# Placa_V_5.net
KiCad netlist of a schematic drawn in EAGLE
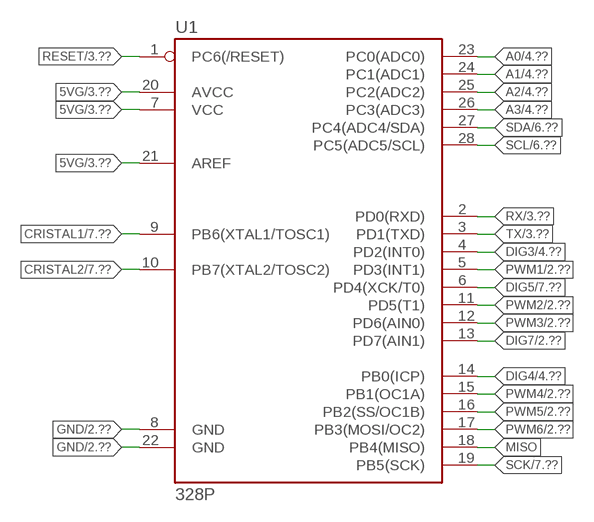
[diagram p0: schematic, sheet 1]
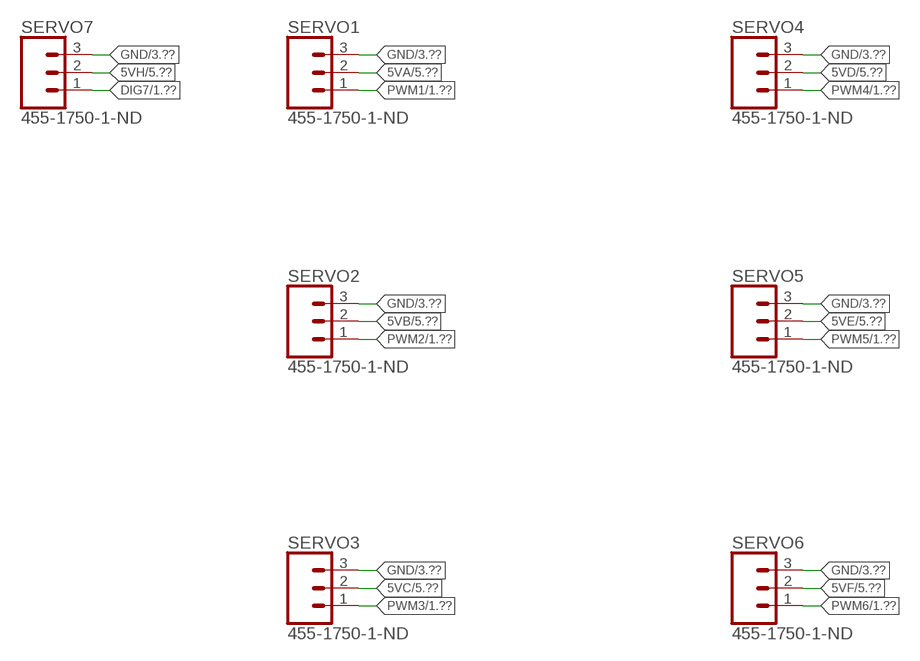
[diagram p1: schematic, sheet 2]
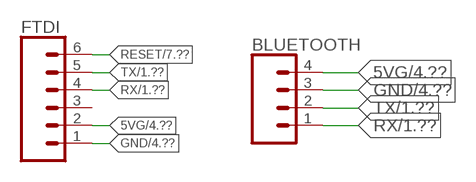
[diagram p2: schematic, sheet 3]
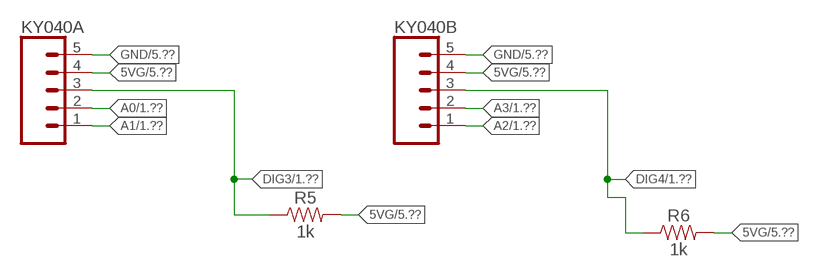
[diagram p3: schematic, sheet 4]
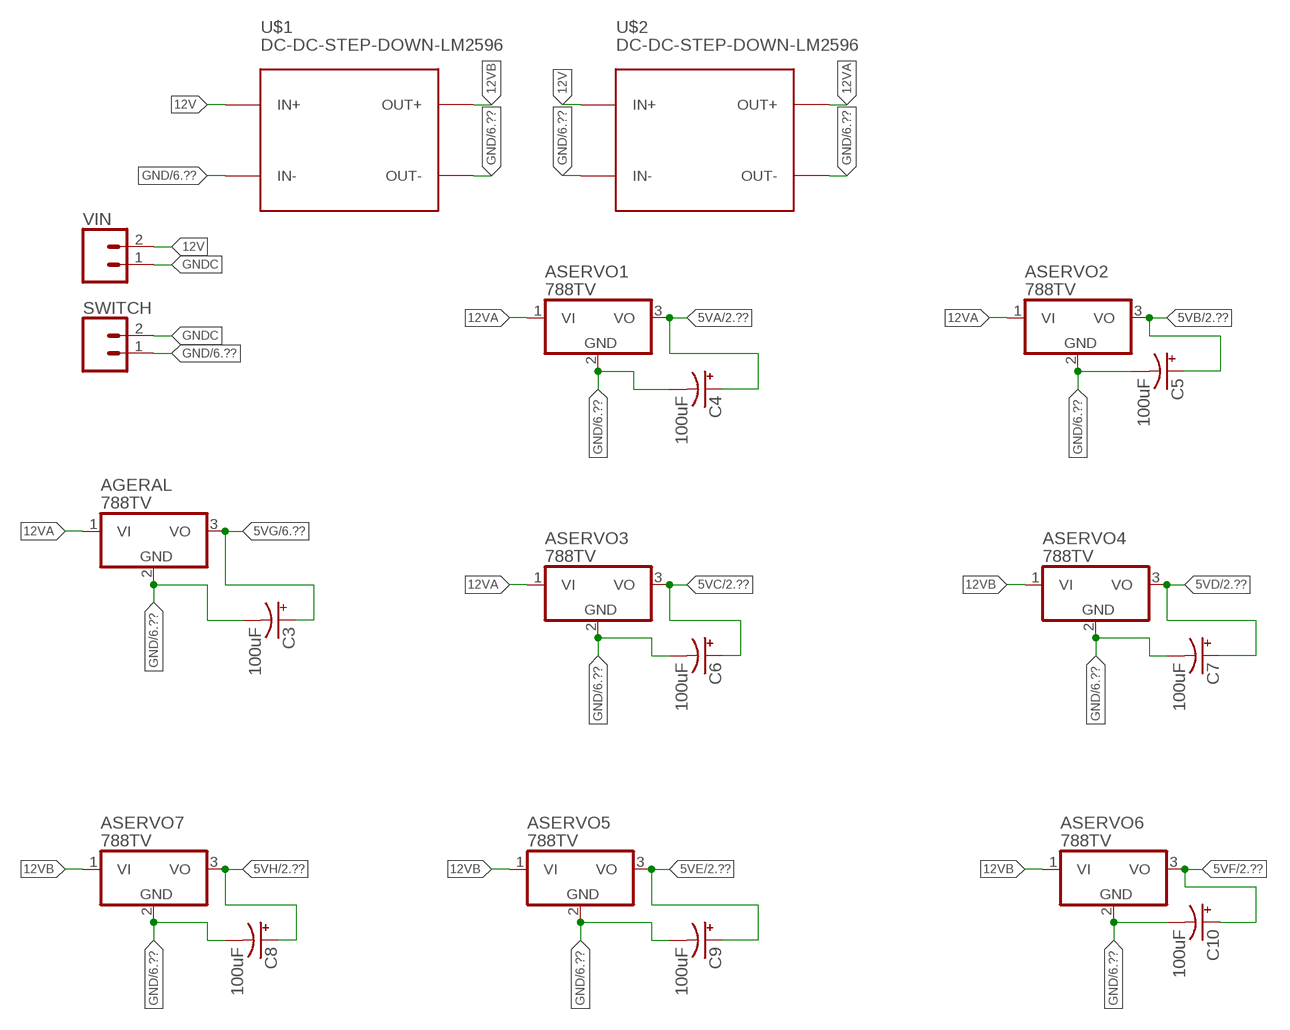
[diagram p4: schematic, sheet 5]
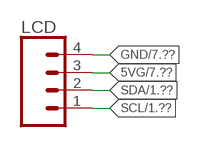
[diagram p5: schematic, sheet 6]
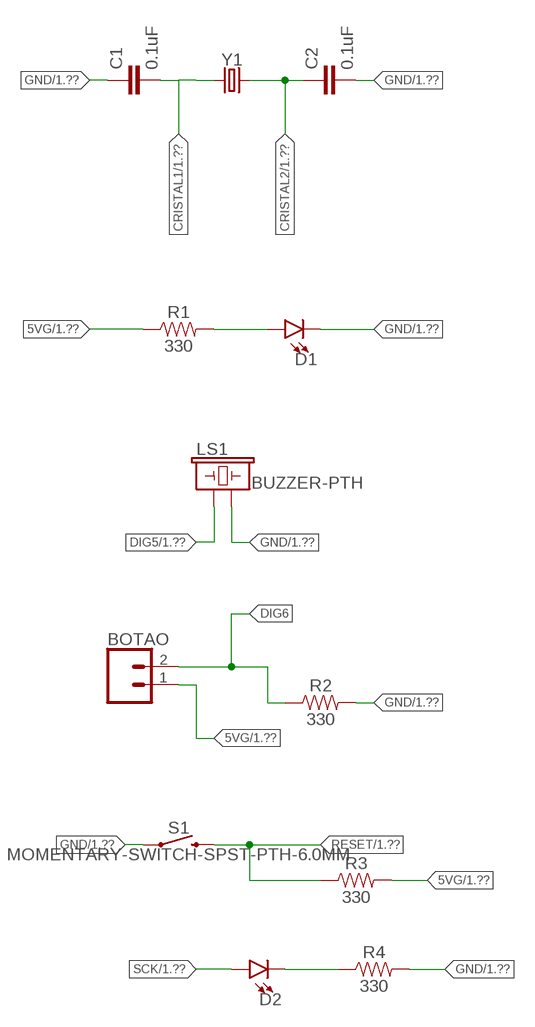
[diagram p6: schematic, sheet 7]

(export (version "E")
  (design (tool "Eeschema 10.0.6"))
  (components
    (comp (ref "AGERAL")
      (value "788TV")
      (footprint "eagle-import:TO220V")
      (libsource (lib "eagle-import") (part "78TV8"))
    )
    (comp (ref "ASERVO1")
      (value "788TV")
      (footprint "eagle-import:TO220V")
      (libsource (lib "eagle-import") (part "78TV8"))
    )
    (comp (ref "ASERVO2")
      (value "788TV")
      (footprint "eagle-import:TO220V")
      (libsource (lib "eagle-import") (part "78TV8"))
    )
    (comp (ref "ASERVO3")
      (value "788TV")
      (footprint "eagle-import:TO220V")
      (libsource (lib "eagle-import") (part "78TV8"))
    )
    (comp (ref "ASERVO4")
      (value "788TV")
      (footprint "eagle-import:TO220V")
      (libsource (lib "eagle-import") (part "78TV8"))
    )
    (comp (ref "ASERVO5")
      (value "788TV")
      (footprint "eagle-import:TO220V")
      (libsource (lib "eagle-import") (part "78TV8"))
    )
    (comp (ref "ASERVO6")
      (value "788TV")
      (footprint "eagle-import:TO220V")
      (libsource (lib "eagle-import") (part "78TV8"))
    )
    (comp (ref "ASERVO7")
      (value "788TV")
      (footprint "eagle-import:TO220V")
      (libsource (lib "eagle-import") (part "78TV8"))
    )
    (comp (ref "C3")
      (value "100uF")
      (footprint "eagle-import:CPOL-RADIAL-2.5MM-6.5MM")
      (libsource (lib "eagle-import") (part "100UF-POLAR-RADIAL-2.5MM-25V-20%"))
    )
    (comp (ref "C4")
      (value "100uF")
      (footprint "eagle-import:CPOL-RADIAL-2.5MM-6.5MM")
      (libsource (lib "eagle-import") (part "100UF-POLAR-RADIAL-2.5MM-25V-20%"))
    )
    (comp (ref "C5")
      (value "100uF")
      (footprint "eagle-import:CPOL-RADIAL-2.5MM-6.5MM")
      (libsource (lib "eagle-import") (part "100UF-POLAR-RADIAL-2.5MM-25V-20%"))
    )
    (comp (ref "C6")
      (value "100uF")
      (footprint "eagle-import:CPOL-RADIAL-2.5MM-6.5MM")
      (libsource (lib "eagle-import") (part "100UF-POLAR-RADIAL-2.5MM-25V-20%"))
    )
    (comp (ref "C7")
      (value "100uF")
      (footprint "eagle-import:CPOL-RADIAL-2.5MM-6.5MM")
      (libsource (lib "eagle-import") (part "100UF-POLAR-RADIAL-2.5MM-25V-20%"))
    )
    (comp (ref "C8")
      (value "100uF")
      (footprint "eagle-import:CPOL-RADIAL-2.5MM-6.5MM")
      (libsource (lib "eagle-import") (part "100UF-POLAR-RADIAL-2.5MM-25V-20%"))
    )
    (comp (ref "C9")
      (value "100uF")
      (footprint "eagle-import:CPOL-RADIAL-2.5MM-6.5MM")
      (libsource (lib "eagle-import") (part "100UF-POLAR-RADIAL-2.5MM-25V-20%"))
    )
    (comp (ref "C10")
      (value "100uF")
      (footprint "eagle-import:CPOL-RADIAL-2.5MM-6.5MM")
      (libsource (lib "eagle-import") (part "100UF-POLAR-RADIAL-2.5MM-25V-20%"))
    )
    (comp (ref "SWITCH")
      (value "CONN_02")
      (footprint "eagle-import:1X02")
      (libsource (lib "eagle-import") (part "CONN_02"))
    )
    (comp (ref "U$1")
      (value "DC-DC-STEP-DOWN-LM2596")
      (footprint "eagle-import:DC-DC-STEP-DOWN-LM2596")
      (libsource (lib "eagle-import") (part "DC-DC-STEP-DOWN-LM2596"))
    )
    (comp (ref "U$2")
      (value "DC-DC-STEP-DOWN-LM2596")
      (footprint "eagle-import:DC-DC-STEP-DOWN-LM2596")
      (libsource (lib "eagle-import") (part "DC-DC-STEP-DOWN-LM2596"))
    )
    (comp (ref "VIN")
      (value "CONN_02")
      (footprint "eagle-import:1X02")
      (libsource (lib "eagle-import") (part "CONN_02"))
    )
    (comp (ref "SERVO1")
      (value "455-1750-1-ND")
      (footprint "eagle-import:1X03")
      (libsource (lib "eagle-import") (part "CONN_03"))
    )
    (comp (ref "SERVO2")
      (value "455-1750-1-ND")
      (footprint "eagle-import:1X03")
      (libsource (lib "eagle-import") (part "CONN_03"))
    )
    (comp (ref "SERVO3")
      (value "455-1750-1-ND")
      (footprint "eagle-import:1X03")
      (libsource (lib "eagle-import") (part "CONN_03"))
    )
    (comp (ref "SERVO4")
      (value "455-1750-1-ND")
      (footprint "eagle-import:1X03")
      (libsource (lib "eagle-import") (part "CONN_03"))
    )
    (comp (ref "SERVO5")
      (value "455-1750-1-ND")
      (footprint "eagle-import:1X03")
      (libsource (lib "eagle-import") (part "CONN_03"))
    )
    (comp (ref "SERVO6")
      (value "455-1750-1-ND")
      (footprint "eagle-import:1X03")
      (libsource (lib "eagle-import") (part "CONN_03"))
    )
    (comp (ref "SERVO7")
      (value "455-1750-1-ND")
      (footprint "eagle-import:1X03")
      (libsource (lib "eagle-import") (part "CONN_03"))
    )
    (comp (ref "KY040A")
      (value "CONN_05")
      (footprint "eagle-import:1X05")
      (libsource (lib "eagle-import") (part "CONN_05"))
    )
    (comp (ref "KY040B")
      (value "CONN_05")
      (footprint "eagle-import:1X05")
      (libsource (lib "eagle-import") (part "CONN_05"))
    )
    (comp (ref "R5")
      (value "1k")
      (footprint "eagle-import:AXIAL-0.3")
      (libsource (lib "eagle-import") (part "1KOHM-HORIZ-1/4W-1%"))
    )
    (comp (ref "R6")
      (value "1k")
      (footprint "eagle-import:AXIAL-0.3")
      (libsource (lib "eagle-import") (part "1KOHM-HORIZ-1/4W-1%"))
    )
    (comp (ref "BOTAO")
      (value "CONN_02")
      (footprint "eagle-import:1X02")
      (libsource (lib "eagle-import") (part "CONN_02"))
    )
    (comp (ref "C1")
      (value "0.1uF")
      (footprint "eagle-import:CAP-PTH-SMALL-KIT")
      (libsource (lib "eagle-import") (part "0.1UF-KIT-EZ-50V-20%"))
    )
    (comp (ref "C2")
      (value "0.1uF")
      (footprint "eagle-import:CAP-PTH-SMALL-KIT")
      (libsource (lib "eagle-import") (part "0.1UF-KIT-EZ-50V-20%"))
    )
    (comp (ref "D1")
      (value "LED5MM")
      (footprint "eagle-import:LED_5MM")
      (libsource (lib "eagle-import") (part "LED5MM"))
    )
    (comp (ref "D2")
      (value "LED5MM")
      (footprint "eagle-import:LED_5MM")
      (libsource (lib "eagle-import") (part "LED5MM"))
    )
    (comp (ref "LS1")
      (value "BUZZER-PTH")
      (footprint "eagle-import:BUZZER-12MM")
      (libsource (lib "eagle-import") (part "BUZZER-PTH"))
    )
    (comp (ref "R1")
      (value "330")
      (footprint "eagle-import:AXIAL-0.3")
      (libsource (lib "eagle-import") (part "330OHM-HORIZ-1/10W-5%"))
    )
    (comp (ref "R2")
      (value "330")
      (footprint "eagle-import:AXIAL-0.3")
      (libsource (lib "eagle-import") (part "330OHM-HORIZ-1/10W-5%"))
    )
    (comp (ref "R3")
      (value "330")
      (footprint "eagle-import:AXIAL-0.3")
      (libsource (lib "eagle-import") (part "330OHM-HORIZ-1/10W-5%"))
    )
    (comp (ref "R4")
      (value "330")
      (footprint "eagle-import:AXIAL-0.3")
      (libsource (lib "eagle-import") (part "330OHM-HORIZ-1/10W-5%"))
    )
    (comp (ref "S1")
      (value "MOMENTARY-SWITCH-SPST-PTH-6.0MM")
      (footprint "eagle-import:TACTILE_SWITCH_PTH_6.0MM")
      (libsource (lib "eagle-import") (part "MOMENTARY-SWITCH-SPST-PTH-6.0MM"))
    )
    (comp (ref "Y1")
      (value "CRYSTALPTH-HC49US")
      (footprint "eagle-import:HC49US")
      (libsource (lib "eagle-import") (part "CRYSTALPTH-HC49US"))
    )
    (comp (ref "BLUETOOTH")
      (value "CONN_04")
      (footprint "eagle-import:1X04")
      (libsource (lib "eagle-import") (part "CONN_04"))
    )
    (comp (ref "FTDI")
      (value "CONN_06SILK_FEMALE_PTH")
      (footprint "eagle-import:1X06")
      (libsource (lib "eagle-import") (part "CONN_06SILK_FEMALE_PTH"))
    )
    (comp (ref "U1")
      (value "328P")
      (footprint "eagle-import:DIP28")
      (libsource (lib "eagle-import") (part "ATMEGA328P_PDIP"))
    )
    (comp (ref "LCD")
      (value "CONN_04")
      (footprint "eagle-import:1X04")
      (libsource (lib "eagle-import") (part "CONN_04"))
    )
  )
  (nets
    (net (code "1") (name "5VA") (class "Default")
      (node (ref "ASERVO1") (pin "3") (pinfunction "VO_3") (pintype "passive"))
      (node (ref "C4") (pin "1") (pinfunction "+_1") (pintype "passive"))
      (node (ref "SERVO1") (pin "2") (pinfunction "2_2") (pintype "passive"))
    )
    (net (code "2") (name "5VB") (class "Default")
      (node (ref "ASERVO2") (pin "3") (pinfunction "VO_3") (pintype "passive"))
      (node (ref "C5") (pin "1") (pinfunction "+_1") (pintype "passive"))
      (node (ref "SERVO2") (pin "2") (pinfunction "2_2") (pintype "passive"))
    )
    (net (code "3") (name "5VC") (class "Default")
      (node (ref "ASERVO3") (pin "3") (pinfunction "VO_3") (pintype "passive"))
      (node (ref "C6") (pin "1") (pinfunction "+_1") (pintype "passive"))
      (node (ref "SERVO3") (pin "2") (pinfunction "2_2") (pintype "passive"))
    )
    (net (code "4") (name "5VD") (class "Default")
      (node (ref "ASERVO4") (pin "3") (pinfunction "VO_3") (pintype "passive"))
      (node (ref "C7") (pin "1") (pinfunction "+_1") (pintype "passive"))
      (node (ref "SERVO4") (pin "2") (pinfunction "2_2") (pintype "passive"))
    )
    (net (code "5") (name "5VE") (class "Default")
      (node (ref "ASERVO5") (pin "3") (pinfunction "VO_3") (pintype "passive"))
      (node (ref "C9") (pin "1") (pinfunction "+_1") (pintype "passive"))
      (node (ref "SERVO5") (pin "2") (pinfunction "2_2") (pintype "passive"))
    )
    (net (code "6") (name "5VF") (class "Default")
      (node (ref "ASERVO6") (pin "3") (pinfunction "VO_3") (pintype "passive"))
      (node (ref "C10") (pin "1") (pinfunction "+_1") (pintype "passive"))
      (node (ref "SERVO6") (pin "2") (pinfunction "2_2") (pintype "passive"))
    )
    (net (code "7") (name "5VG") (class "Default")
      (node (ref "AGERAL") (pin "3") (pinfunction "VO_3") (pintype "passive"))
      (node (ref "BLUETOOTH") (pin "4") (pinfunction "4_4") (pintype "passive"))
      (node (ref "BOTAO") (pin "1") (pinfunction "1_1") (pintype "passive"))
      (node (ref "C3") (pin "1") (pinfunction "+_1") (pintype "passive"))
      (node (ref "FTDI") (pin "2") (pinfunction "2_2") (pintype "passive"))
      (node (ref "KY040A") (pin "4") (pinfunction "4_4") (pintype "passive"))
      (node (ref "KY040B") (pin "4") (pinfunction "4_4") (pintype "passive"))
      (node (ref "LCD") (pin "3") (pinfunction "3_3") (pintype "passive"))
      (node (ref "R1") (pin "P$1") (pinfunction "1_P$1") (pintype "passive"))
      (node (ref "R3") (pin "P$2") (pinfunction "2_P$2") (pintype "passive"))
      (node (ref "R5") (pin "P$2") (pinfunction "2_P$2") (pintype "passive"))
      (node (ref "R6") (pin "P$2") (pinfunction "2_P$2") (pintype "passive"))
      (node (ref "U1") (pin "20") (pinfunction "AVCC_20") (pintype "bidirectional"))
      (node (ref "U1") (pin "21") (pinfunction "AREF_21") (pintype "bidirectional"))
      (node (ref "U1") (pin "7") (pinfunction "VCC_7") (pintype "bidirectional"))
    )
    (net (code "8") (name "5VH") (class "Default")
      (node (ref "ASERVO7") (pin "3") (pinfunction "VO_3") (pintype "passive"))
      (node (ref "C8") (pin "1") (pinfunction "+_1") (pintype "passive"))
      (node (ref "SERVO7") (pin "2") (pinfunction "2_2") (pintype "passive"))
    )
    (net (code "9") (name "12V") (class "Default")
      (node (ref "U$1") (pin "IN+") (pinfunction "IN+_IN+") (pintype "bidirectional"))
      (node (ref "U$2") (pin "IN+") (pinfunction "IN+_IN+") (pintype "bidirectional"))
      (node (ref "VIN") (pin "2") (pinfunction "2_2") (pintype "passive"))
    )
    (net (code "10") (name "12VA") (class "Default")
      (node (ref "AGERAL") (pin "1") (pinfunction "VI_1") (pintype "input"))
      (node (ref "ASERVO1") (pin "1") (pinfunction "VI_1") (pintype "input"))
      (node (ref "ASERVO2") (pin "1") (pinfunction "VI_1") (pintype "input"))
      (node (ref "ASERVO3") (pin "1") (pinfunction "VI_1") (pintype "input"))
      (node (ref "U$2") (pin "OUT+") (pinfunction "OUT+_OUT+") (pintype "bidirectional"))
    )
    (net (code "11") (name "12VB") (class "Default")
      (node (ref "ASERVO4") (pin "1") (pinfunction "VI_1") (pintype "input"))
      (node (ref "ASERVO5") (pin "1") (pinfunction "VI_1") (pintype "input"))
      (node (ref "ASERVO6") (pin "1") (pinfunction "VI_1") (pintype "input"))
      (node (ref "ASERVO7") (pin "1") (pinfunction "VI_1") (pintype "input"))
      (node (ref "U$1") (pin "OUT+") (pinfunction "OUT+_OUT+") (pintype "bidirectional"))
    )
    (net (code "12") (name "A0") (class "Default")
      (node (ref "KY040A") (pin "2") (pinfunction "2_2") (pintype "passive"))
      (node (ref "U1") (pin "23") (pinfunction "PC0(ADC0)_23") (pintype "bidirectional"))
    )
    (net (code "13") (name "A1") (class "Default")
      (node (ref "KY040A") (pin "1") (pinfunction "1_1") (pintype "passive"))
      (node (ref "U1") (pin "24") (pinfunction "PC1(ADC1)_24") (pintype "bidirectional"))
    )
    (net (code "14") (name "A2") (class "Default")
      (node (ref "KY040B") (pin "1") (pinfunction "1_1") (pintype "passive"))
      (node (ref "U1") (pin "25") (pinfunction "PC2(ADC2)_25") (pintype "bidirectional"))
    )
    (net (code "15") (name "A3") (class "Default")
      (node (ref "KY040B") (pin "2") (pinfunction "2_2") (pintype "passive"))
      (node (ref "U1") (pin "26") (pinfunction "PC3(ADC3)_26") (pintype "bidirectional"))
    )
    (net (code "16") (name "CRISTAL1") (class "Default")
      (node (ref "C1") (pin "2") (pinfunction "2_2") (pintype "passive"))
      (node (ref "U1") (pin "9") (pinfunction "PB6(XTAL1/TOSC1)_9") (pintype "bidirectional"))
      (node (ref "Y1") (pin "1") (pinfunction "1_1") (pintype "passive"))
    )
    (net (code "17") (name "CRISTAL2") (class "Default")
      (node (ref "C2") (pin "1") (pinfunction "1_1") (pintype "passive"))
      (node (ref "U1") (pin "10") (pinfunction "PB7(XTAL2/TOSC2)_10") (pintype "bidirectional"))
      (node (ref "Y1") (pin "2") (pinfunction "2_2") (pintype "passive"))
    )
    (net (code "18") (name "DIG3") (class "Default")
      (node (ref "KY040A") (pin "3") (pinfunction "3_3") (pintype "passive"))
      (node (ref "R5") (pin "P$1") (pinfunction "1_P$1") (pintype "passive"))
      (node (ref "U1") (pin "4") (pinfunction "PD2(INT0)_4") (pintype "bidirectional"))
    )
    (net (code "19") (name "DIG4") (class "Default")
      (node (ref "KY040B") (pin "3") (pinfunction "3_3") (pintype "passive"))
      (node (ref "R6") (pin "P$1") (pinfunction "1_P$1") (pintype "passive"))
      (node (ref "U1") (pin "14") (pinfunction "PB0(ICP)_14") (pintype "bidirectional"))
    )
    (net (code "20") (name "DIG5") (class "Default")
      (node (ref "LS1") (pin "+") (pinfunction "1_+") (pintype "passive"))
      (node (ref "U1") (pin "6") (pinfunction "PD4(XCK/T0)_6") (pintype "bidirectional"))
    )
    (net (code "21") (name "DIG6") (class "Default")
      (node (ref "BOTAO") (pin "2") (pinfunction "2_2") (pintype "passive"))
      (node (ref "R2") (pin "P$1") (pinfunction "1_P$1") (pintype "passive"))
    )
    (net (code "22") (name "DIG7") (class "Default")
      (node (ref "SERVO7") (pin "1") (pinfunction "1_1") (pintype "passive"))
      (node (ref "U1") (pin "13") (pinfunction "PD7(AIN1)_13") (pintype "bidirectional"))
    )
    (net (code "23") (name "GND") (class "Default")
      (node (ref "AGERAL") (pin "2") (pinfunction "GND_2") (pintype "passive"))
      (node (ref "ASERVO1") (pin "2") (pinfunction "GND_2") (pintype "passive"))
      (node (ref "ASERVO2") (pin "2") (pinfunction "GND_2") (pintype "passive"))
      (node (ref "ASERVO3") (pin "2") (pinfunction "GND_2") (pintype "passive"))
      (node (ref "ASERVO4") (pin "2") (pinfunction "GND_2") (pintype "passive"))
      (node (ref "ASERVO5") (pin "2") (pinfunction "GND_2") (pintype "passive"))
      (node (ref "ASERVO6") (pin "2") (pinfunction "GND_2") (pintype "passive"))
      (node (ref "ASERVO7") (pin "2") (pinfunction "GND_2") (pintype "passive"))
      (node (ref "BLUETOOTH") (pin "3") (pinfunction "3_3") (pintype "passive"))
      (node (ref "C1") (pin "1") (pinfunction "1_1") (pintype "passive"))
      (node (ref "C10") (pin "2") (pinfunction "-_2") (pintype "passive"))
      (node (ref "C2") (pin "2") (pinfunction "2_2") (pintype "passive"))
      (node (ref "C3") (pin "2") (pinfunction "-_2") (pintype "passive"))
      (node (ref "C4") (pin "2") (pinfunction "-_2") (pintype "passive"))
      (node (ref "C5") (pin "2") (pinfunction "-_2") (pintype "passive"))
      (node (ref "C6") (pin "2") (pinfunction "-_2") (pintype "passive"))
      (node (ref "C7") (pin "2") (pinfunction "-_2") (pintype "passive"))
      (node (ref "C8") (pin "2") (pinfunction "-_2") (pintype "passive"))
      (node (ref "C9") (pin "2") (pinfunction "-_2") (pintype "passive"))
      (node (ref "D1") (pin "K") (pinfunction "C_K") (pintype "passive"))
      (node (ref "FTDI") (pin "1") (pinfunction "1_1") (pintype "passive"))
      (node (ref "KY040A") (pin "5") (pinfunction "5_5") (pintype "passive"))
      (node (ref "KY040B") (pin "5") (pinfunction "5_5") (pintype "passive"))
      (node (ref "LCD") (pin "4") (pinfunction "4_4") (pintype "passive"))
      (node (ref "LS1") (pin "-") (pinfunction "2_-") (pintype "passive"))
      (node (ref "R2") (pin "P$2") (pinfunction "2_P$2") (pintype "passive"))
      (node (ref "R4") (pin "P$2") (pinfunction "2_P$2") (pintype "passive"))
      (node (ref "S1") (pin "1") (pinfunction "1_1") (pintype "passive"))
      (node (ref "SERVO1") (pin "3") (pinfunction "3_3") (pintype "passive"))
      (node (ref "SERVO2") (pin "3") (pinfunction "3_3") (pintype "passive"))
      (node (ref "SERVO3") (pin "3") (pinfunction "3_3") (pintype "passive"))
      (node (ref "SERVO4") (pin "3") (pinfunction "3_3") (pintype "passive"))
      (node (ref "SERVO5") (pin "3") (pinfunction "3_3") (pintype "passive"))
      (node (ref "SERVO6") (pin "3") (pinfunction "3_3") (pintype "passive"))
      (node (ref "SERVO7") (pin "3") (pinfunction "3_3") (pintype "passive"))
      (node (ref "SWITCH") (pin "1") (pinfunction "1_1") (pintype "passive"))
      (node (ref "U$1") (pin "IN-") (pinfunction "IN-_IN-") (pintype "bidirectional"))
      (node (ref "U$1") (pin "OUT-") (pinfunction "OUT-_OUT-") (pintype "bidirectional"))
      (node (ref "U$2") (pin "IN-") (pinfunction "IN-_IN-") (pintype "bidirectional"))
      (node (ref "U$2") (pin "OUT-") (pinfunction "OUT-_OUT-") (pintype "bidirectional"))
      (node (ref "U1") (pin "22") (pinfunction "GND_22") (pintype "bidirectional"))
      (node (ref "U1") (pin "8") (pinfunction "GND_8") (pintype "bidirectional"))
    )
    (net (code "24") (name "GNDC") (class "Default")
      (node (ref "SWITCH") (pin "2") (pinfunction "2_2") (pintype "passive"))
      (node (ref "VIN") (pin "1") (pinfunction "1_1") (pintype "passive"))
    )
    (net (code "25") (name "MISO") (class "Default")
      (node (ref "U1") (pin "18") (pinfunction "PB4(MISO)_18") (pintype "bidirectional"))
    )
    (net (code "26") (name "Net-(D2-C)") (class "Default")
      (node (ref "D2") (pin "K") (pinfunction "C_K") (pintype "passive"))
      (node (ref "R4") (pin "P$1") (pinfunction "1_P$1") (pintype "passive"))
    )
    (net (code "27") (name "Net-(R1-2)") (class "Default")
      (node (ref "D1") (pin "A") (pinfunction "A_A") (pintype "passive"))
      (node (ref "R1") (pin "P$2") (pinfunction "2_P$2") (pintype "passive"))
    )
    (net (code "28") (name "PWM1") (class "Default")
      (node (ref "SERVO1") (pin "1") (pinfunction "1_1") (pintype "passive"))
      (node (ref "U1") (pin "5") (pinfunction "PD3(INT1)_5") (pintype "bidirectional"))
    )
    (net (code "29") (name "PWM2") (class "Default")
      (node (ref "SERVO2") (pin "1") (pinfunction "1_1") (pintype "passive"))
      (node (ref "U1") (pin "11") (pinfunction "PD5(T1)_11") (pintype "bidirectional"))
    )
    (net (code "30") (name "PWM3") (class "Default")
      (node (ref "SERVO3") (pin "1") (pinfunction "1_1") (pintype "passive"))
      (node (ref "U1") (pin "12") (pinfunction "PD6(AIN0)_12") (pintype "bidirectional"))
    )
    (net (code "31") (name "PWM4") (class "Default")
      (node (ref "SERVO4") (pin "1") (pinfunction "1_1") (pintype "passive"))
      (node (ref "U1") (pin "15") (pinfunction "PB1(OC1A)_15") (pintype "bidirectional"))
    )
    (net (code "32") (name "PWM5") (class "Default")
      (node (ref "SERVO5") (pin "1") (pinfunction "1_1") (pintype "passive"))
      (node (ref "U1") (pin "16") (pinfunction "PB2(SS/OC1B)_16") (pintype "bidirectional"))
    )
    (net (code "33") (name "PWM6") (class "Default")
      (node (ref "SERVO6") (pin "1") (pinfunction "1_1") (pintype "passive"))
      (node (ref "U1") (pin "17") (pinfunction "PB3(MOSI/OC2)_17") (pintype "bidirectional"))
    )
    (net (code "34") (name "RESET") (class "Default")
      (node (ref "FTDI") (pin "6") (pinfunction "6_6") (pintype "passive"))
      (node (ref "R3") (pin "P$1") (pinfunction "1_P$1") (pintype "passive"))
      (node (ref "S1") (pin "3") (pinfunction "2_3") (pintype "passive"))
      (node (ref "U1") (pin "1") (pinfunction "PC6(/RESET)_1") (pintype "bidirectional"))
    )
    (net (code "35") (name "RX") (class "Default")
      (node (ref "BLUETOOTH") (pin "1") (pinfunction "1_1") (pintype "passive"))
      (node (ref "FTDI") (pin "4") (pinfunction "4_4") (pintype "passive"))
      (node (ref "U1") (pin "2") (pinfunction "PD0(RXD)_2") (pintype "bidirectional"))
    )
    (net (code "36") (name "SCK") (class "Default")
      (node (ref "D2") (pin "A") (pinfunction "A_A") (pintype "passive"))
      (node (ref "U1") (pin "19") (pinfunction "PB5(SCK)_19") (pintype "bidirectional"))
    )
    (net (code "37") (name "SCL") (class "Default")
      (node (ref "LCD") (pin "1") (pinfunction "1_1") (pintype "passive"))
      (node (ref "U1") (pin "28") (pinfunction "PC5(ADC5/SCL)_28") (pintype "bidirectional"))
    )
    (net (code "38") (name "SDA") (class "Default")
      (node (ref "LCD") (pin "2") (pinfunction "2_2") (pintype "passive"))
      (node (ref "U1") (pin "27") (pinfunction "PC4(ADC4/SDA)_27") (pintype "bidirectional"))
    )
    (net (code "39") (name "TX") (class "Default")
      (node (ref "BLUETOOTH") (pin "2") (pinfunction "2_2") (pintype "passive"))
      (node (ref "FTDI") (pin "5") (pinfunction "5_5") (pintype "passive"))
      (node (ref "U1") (pin "3") (pinfunction "PD1(TXD)_3") (pintype "bidirectional"))
    )
    (net (code "40") (name "unconnected-(FTDI-Pad3)") (class "Default")
      (node (ref "FTDI") (pin "3") (pinfunction "3_3") (pintype "passive"))
    )
  )
)
